# OpenAg_Signals_V6.net
KiCad netlist of a schematic drawn in EAGLE
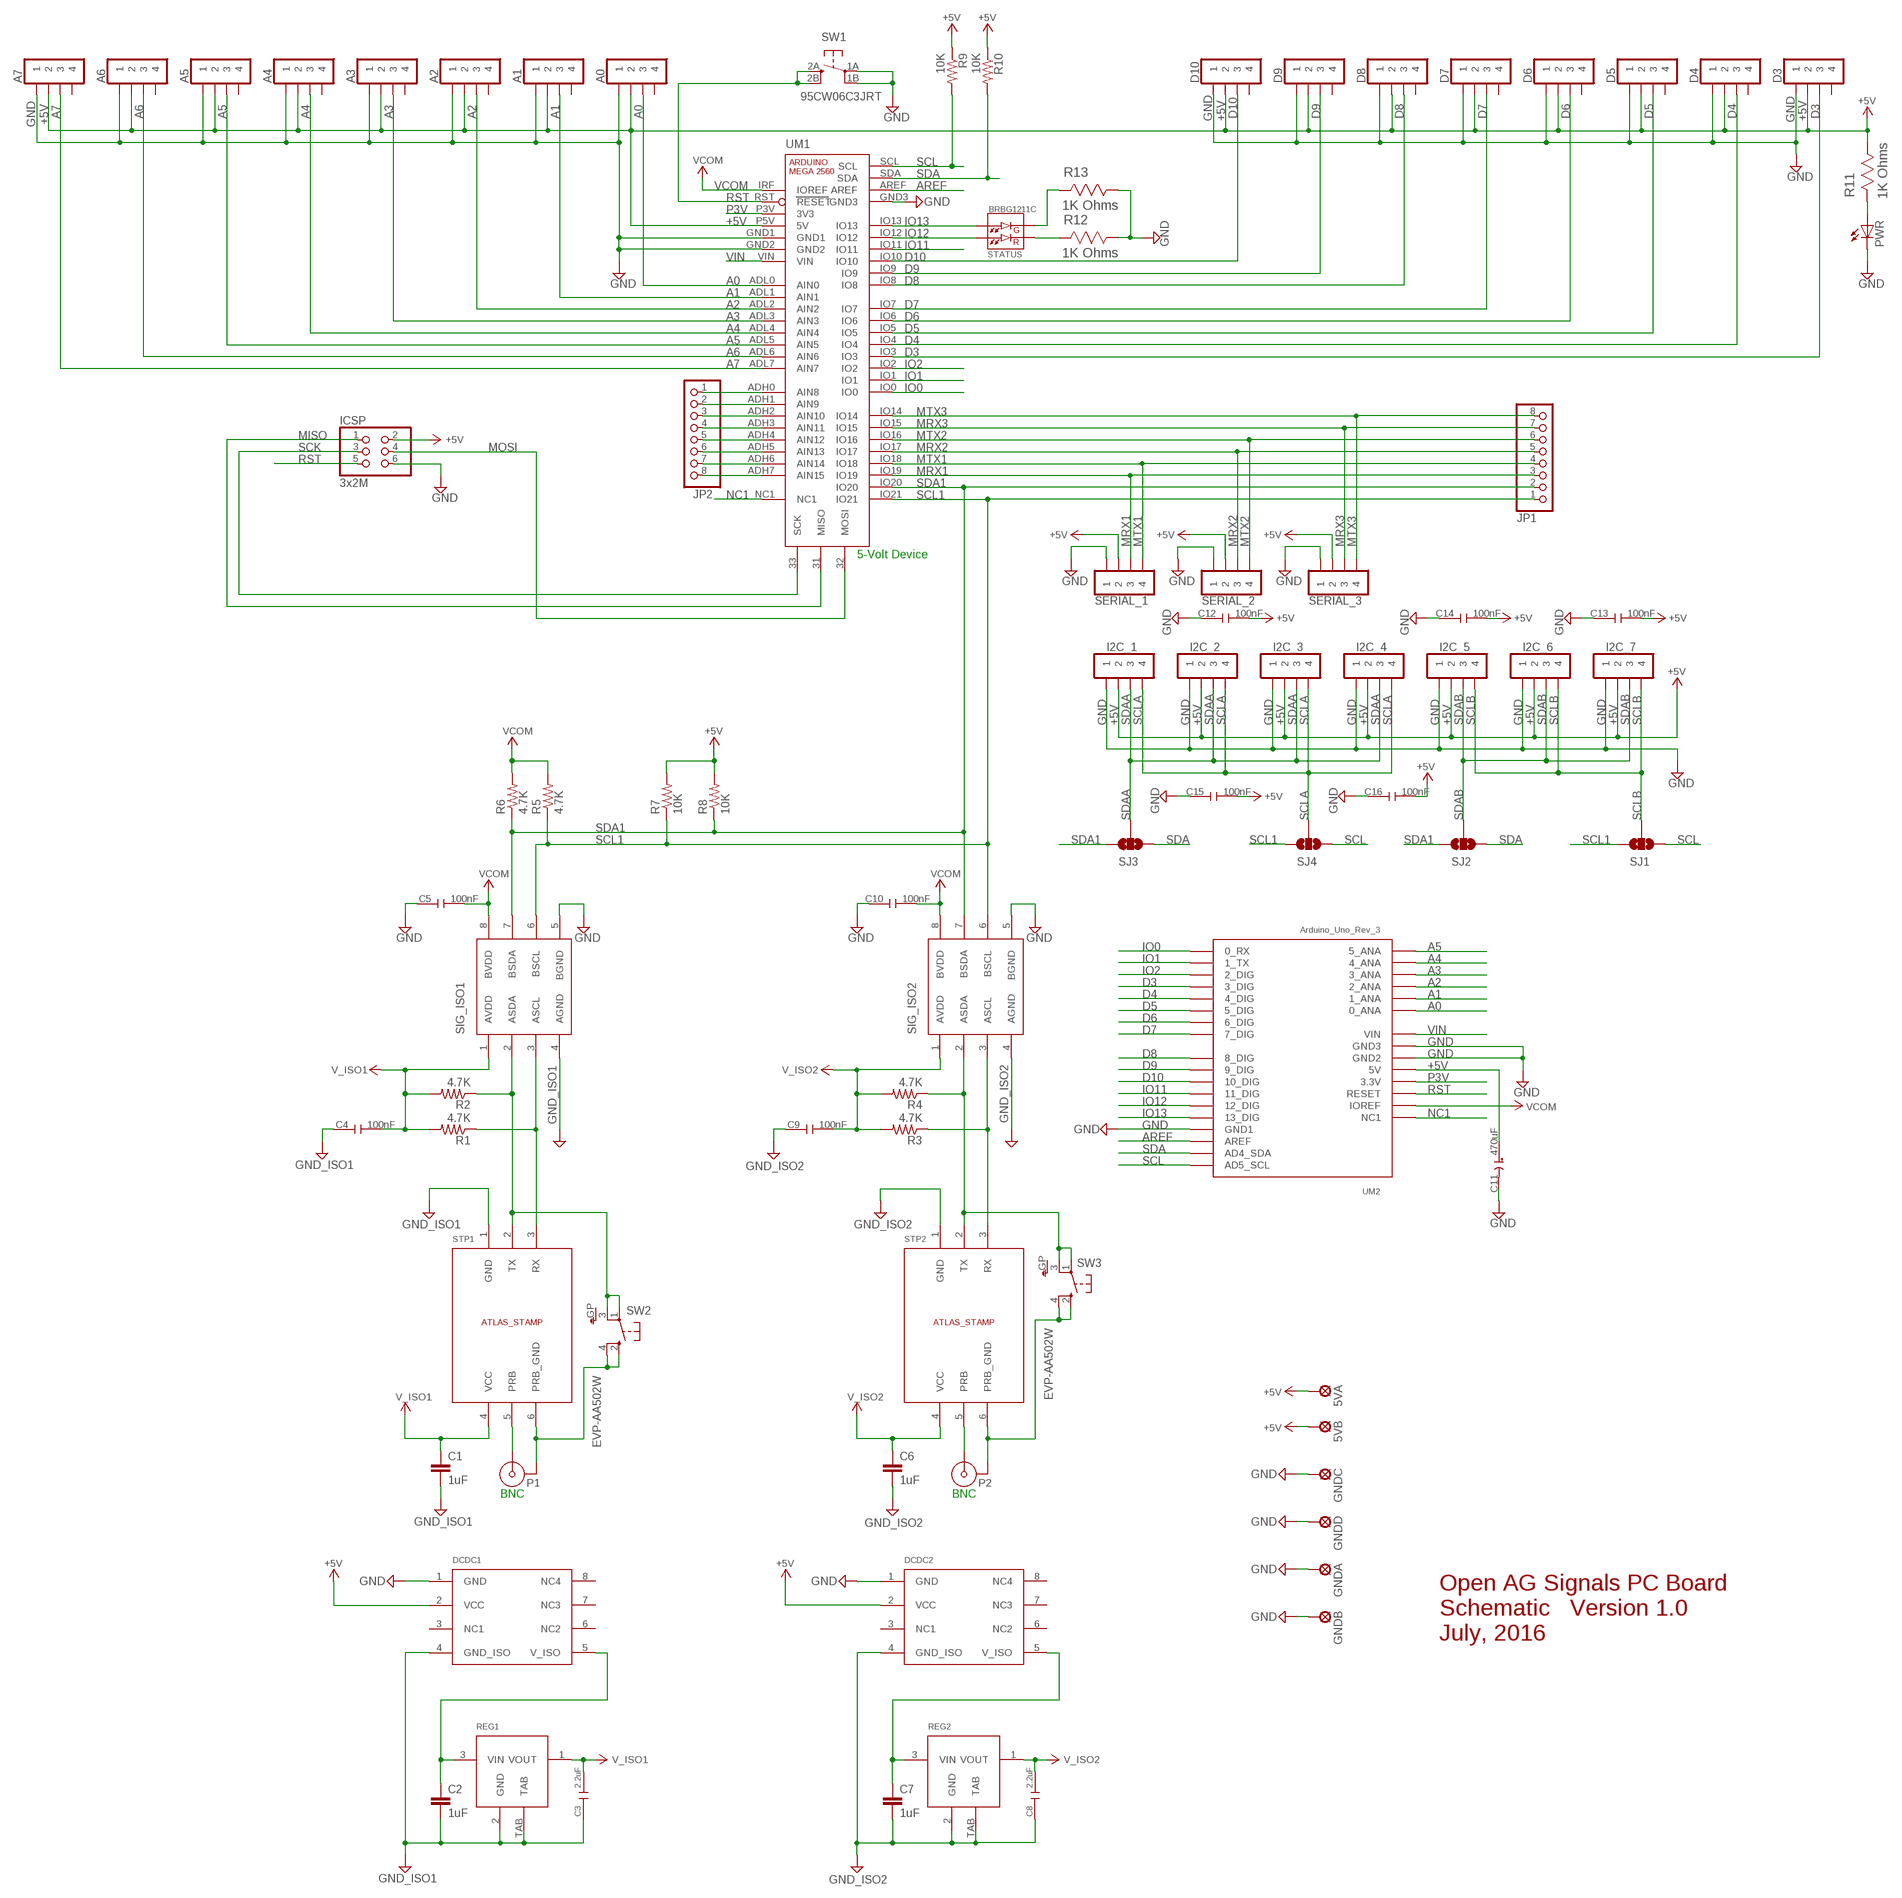
[diagram p0: schematic, sheet 1]

(export (version "E")
  (design (tool "Eeschema 10.0.6"))
  (components
    (comp (ref "5VA")
      (value "PAD070")
      (footprint "eagle-import:PAD070")
      (libsource (lib "eagle-import") (part "PAD070"))
    )
    (comp (ref "5VB")
      (value "PAD070")
      (footprint "eagle-import:PAD070")
      (libsource (lib "eagle-import") (part "PAD070"))
    )
    (comp (ref "A0")
      (value "MOLEX_0705430003")
      (footprint "eagle-import:MOLEX_0705430003")
      (libsource (lib "eagle-import") (part "MOLEX_0705430003"))
    )
    (comp (ref "A1")
      (value "MOLEX_0705430003")
      (footprint "eagle-import:MOLEX_0705430003")
      (libsource (lib "eagle-import") (part "MOLEX_0705430003"))
    )
    (comp (ref "A2")
      (value "MOLEX_0705430003")
      (footprint "eagle-import:MOLEX_0705430003")
      (libsource (lib "eagle-import") (part "MOLEX_0705430003"))
    )
    (comp (ref "A3")
      (value "MOLEX_0705430003")
      (footprint "eagle-import:MOLEX_0705430003")
      (libsource (lib "eagle-import") (part "MOLEX_0705430003"))
    )
    (comp (ref "A4")
      (value "MOLEX_0705430003")
      (footprint "eagle-import:MOLEX_0705430003")
      (libsource (lib "eagle-import") (part "MOLEX_0705430003"))
    )
    (comp (ref "A5")
      (value "MOLEX_0705430003")
      (footprint "eagle-import:MOLEX_0705430003")
      (libsource (lib "eagle-import") (part "MOLEX_0705430003"))
    )
    (comp (ref "A6")
      (value "MOLEX_0705430003")
      (footprint "eagle-import:MOLEX_0705430003")
      (libsource (lib "eagle-import") (part "MOLEX_0705430003"))
    )
    (comp (ref "A7")
      (value "MOLEX_0705430003")
      (footprint "eagle-import:MOLEX_0705430003")
      (libsource (lib "eagle-import") (part "MOLEX_0705430003"))
    )
    (comp (ref "C1")
      (value "1uF")
      (footprint "eagle-import:0805")
      (libsource (lib "eagle-import") (part "1UF-25V-10%(0805)"))
    )
    (comp (ref "C2")
      (value "1uF")
      (footprint "eagle-import:0805")
      (libsource (lib "eagle-import") (part "1UF-25V-10%(0805)"))
    )
    (comp (ref "C3")
      (value "2.2uF")
      (footprint "eagle-import:M0805")
      (libsource (lib "eagle-import") (part "CGA4J1X7R1V225K125AC"))
    )
    (comp (ref "C4")
      (value "C-N-100.0N-X7R-25V-10P-0805")
      (footprint "eagle-import:M0805")
      (libsource (lib "eagle-import") (part "C--?0805N-100.0N-X7R-25V-10P"))
    )
    (comp (ref "C5")
      (value "C-N-100.0N-X7R-25V-10P-0805")
      (footprint "eagle-import:M0805")
      (libsource (lib "eagle-import") (part "C--?0805N-100.0N-X7R-25V-10P"))
    )
    (comp (ref "C6")
      (value "1uF")
      (footprint "eagle-import:0805")
      (libsource (lib "eagle-import") (part "1UF-25V-10%(0805)"))
    )
    (comp (ref "C7")
      (value "1uF")
      (footprint "eagle-import:0805")
      (libsource (lib "eagle-import") (part "1UF-25V-10%(0805)"))
    )
    (comp (ref "C8")
      (value "2.2uF")
      (footprint "eagle-import:M0805")
      (libsource (lib "eagle-import") (part "CGA4J1X7R1V225K125AC"))
    )
    (comp (ref "C9")
      (value "C-N-100.0N-X7R-25V-10P-0805")
      (footprint "eagle-import:M0805")
      (libsource (lib "eagle-import") (part "C--?0805N-100.0N-X7R-25V-10P"))
    )
    (comp (ref "C10")
      (value "C-N-100.0N-X7R-25V-10P-0805")
      (footprint "eagle-import:M0805")
      (libsource (lib "eagle-import") (part "C--?0805N-100.0N-X7R-25V-10P"))
    )
    (comp (ref "C11")
      (value "T495X477K010ATE100")
      (footprint "eagle-import:M2917")
      (libsource (lib "eagle-import") (part "T495X477K010ATE100"))
    )
    (comp (ref "C12")
      (value "C-N-100.0N-X7R-25V-10P-0805")
      (footprint "eagle-import:M0805")
      (libsource (lib "eagle-import") (part "C--?0805N-100.0N-X7R-25V-10P"))
    )
    (comp (ref "C13")
      (value "C-N-100.0N-X7R-25V-10P-0805")
      (footprint "eagle-import:M0805")
      (libsource (lib "eagle-import") (part "C--?0805N-100.0N-X7R-25V-10P"))
    )
    (comp (ref "C14")
      (value "C-N-100.0N-X7R-25V-10P-0805")
      (footprint "eagle-import:M0805")
      (libsource (lib "eagle-import") (part "C--?0805N-100.0N-X7R-25V-10P"))
    )
    (comp (ref "C15")
      (value "C-N-100.0N-X7R-25V-10P-0805")
      (footprint "eagle-import:M0805")
      (libsource (lib "eagle-import") (part "C--?0805N-100.0N-X7R-25V-10P"))
    )
    (comp (ref "C16")
      (value "C-N-100.0N-X7R-25V-10P-0805")
      (footprint "eagle-import:M0805")
      (libsource (lib "eagle-import") (part "C--?0805N-100.0N-X7R-25V-10P"))
    )
    (comp (ref "D3")
      (value "MOLEX_0705430003")
      (footprint "eagle-import:MOLEX_0705430003")
      (libsource (lib "eagle-import") (part "MOLEX_0705430003"))
    )
    (comp (ref "D4")
      (value "MOLEX_0705430003")
      (footprint "eagle-import:MOLEX_0705430003")
      (libsource (lib "eagle-import") (part "MOLEX_0705430003"))
    )
    (comp (ref "D5")
      (value "MOLEX_0705430003")
      (footprint "eagle-import:MOLEX_0705430003")
      (libsource (lib "eagle-import") (part "MOLEX_0705430003"))
    )
    (comp (ref "D6")
      (value "MOLEX_0705430003")
      (footprint "eagle-import:MOLEX_0705430003")
      (libsource (lib "eagle-import") (part "MOLEX_0705430003"))
    )
    (comp (ref "D7")
      (value "MOLEX_0705430003")
      (footprint "eagle-import:MOLEX_0705430003")
      (libsource (lib "eagle-import") (part "MOLEX_0705430003"))
    )
    (comp (ref "D8")
      (value "MOLEX_0705430003")
      (footprint "eagle-import:MOLEX_0705430003")
      (libsource (lib "eagle-import") (part "MOLEX_0705430003"))
    )
    (comp (ref "D9")
      (value "MOLEX_0705430003")
      (footprint "eagle-import:MOLEX_0705430003")
      (libsource (lib "eagle-import") (part "MOLEX_0705430003"))
    )
    (comp (ref "D10")
      (value "MOLEX_0705430003")
      (footprint "eagle-import:MOLEX_0705430003")
      (libsource (lib "eagle-import") (part "MOLEX_0705430003"))
    )
    (comp (ref "DCDC1")
      (value "RECOM_R1SE_0505_R")
      (footprint "eagle-import:RECOM_R1SE_0505_R")
      (libsource (lib "eagle-import") (part "RECOM_R1SE_0505_R"))
    )
    (comp (ref "DCDC2")
      (value "RECOM_R1SE_0505_R")
      (footprint "eagle-import:RECOM_R1SE_0505_R")
      (libsource (lib "eagle-import") (part "RECOM_R1SE_0505_R"))
    )
    (comp (ref "GNDA")
      (value "PAD070")
      (footprint "eagle-import:PAD070")
      (libsource (lib "eagle-import") (part "PAD070"))
    )
    (comp (ref "GNDB")
      (value "PAD070")
      (footprint "eagle-import:PAD070")
      (libsource (lib "eagle-import") (part "PAD070"))
    )
    (comp (ref "GNDC")
      (value "PAD070")
      (footprint "eagle-import:PAD070")
      (libsource (lib "eagle-import") (part "PAD070"))
    )
    (comp (ref "GNDD")
      (value "PAD070")
      (footprint "eagle-import:PAD070")
      (libsource (lib "eagle-import") (part "PAD070"))
    )
    (comp (ref "I2C_1")
      (value "MOLEX_0705430003")
      (footprint "eagle-import:MOLEX_0705430003")
      (libsource (lib "eagle-import") (part "MOLEX_0705430003"))
    )
    (comp (ref "I2C_2")
      (value "MOLEX_0705430003")
      (footprint "eagle-import:MOLEX_0705430003")
      (libsource (lib "eagle-import") (part "MOLEX_0705430003"))
    )
    (comp (ref "I2C_3")
      (value "MOLEX_0705430003")
      (footprint "eagle-import:MOLEX_0705430003")
      (libsource (lib "eagle-import") (part "MOLEX_0705430003"))
    )
    (comp (ref "I2C_4")
      (value "MOLEX_0705430003")
      (footprint "eagle-import:MOLEX_0705430003")
      (libsource (lib "eagle-import") (part "MOLEX_0705430003"))
    )
    (comp (ref "I2C_5")
      (value "MOLEX_0705430003")
      (footprint "eagle-import:MOLEX_0705430003")
      (libsource (lib "eagle-import") (part "MOLEX_0705430003"))
    )
    (comp (ref "I2C_6")
      (value "MOLEX_0705430003")
      (footprint "eagle-import:MOLEX_0705430003")
      (libsource (lib "eagle-import") (part "MOLEX_0705430003"))
    )
    (comp (ref "I2C_7")
      (value "MOLEX_0705430003")
      (footprint "eagle-import:MOLEX_0705430003")
      (libsource (lib "eagle-import") (part "MOLEX_0705430003"))
    )
    (comp (ref "ICSP")
      (value "3x2M")
      (footprint "eagle-import:2X03")
      (libsource (lib "eagle-import") (part "PINHD-2X3"))
    )
    (comp (ref "JP1")
      (value "PINHD-1X8BIG")
      (footprint "eagle-import:1X08-BIG")
      (libsource (lib "eagle-import") (part "PINHD-1X8BIG"))
    )
    (comp (ref "JP2")
      (value "PINHD-1X8BIG")
      (footprint "eagle-import:1X08-BIG")
      (libsource (lib "eagle-import") (part "PINHD-1X8BIG"))
    )
    (comp (ref "P1")
      (value "BNC_TE_1_1337542_0")
      (footprint "eagle-import:BNC_FEMALE_PANEL_RGT_ANGLE_MNT")
      (libsource (lib "eagle-import") (part "BNC_TE_1_1337542_0"))
    )
    (comp (ref "P2")
      (value "BNC_TE_1_1337542_0")
      (footprint "eagle-import:BNC_FEMALE_PANEL_RGT_ANGLE_MNT")
      (libsource (lib "eagle-import") (part "BNC_TE_1_1337542_0"))
    )
    (comp (ref "PWR")
      (value "LED_LEDCHIPLED_0805")
      (footprint "eagle-import:LED_CHIPLED_0805")
      (libsource (lib "eagle-import") (part "LED_LEDCHIPLED_0805"))
    )
    (comp (ref "R1")
      (value "4.7K")
      (footprint "eagle-import:0805")
      (libsource (lib "eagle-import") (part "RESISTOR"))
    )
    (comp (ref "R2")
      (value "4.7K")
      (footprint "eagle-import:0805")
      (libsource (lib "eagle-import") (part "RESISTOR"))
    )
    (comp (ref "R3")
      (value "4.7K")
      (footprint "eagle-import:0805")
      (libsource (lib "eagle-import") (part "RESISTOR"))
    )
    (comp (ref "R4")
      (value "4.7K")
      (footprint "eagle-import:0805")
      (libsource (lib "eagle-import") (part "RESISTOR"))
    )
    (comp (ref "R5")
      (value "4.7K")
      (footprint "eagle-import:0805")
      (libsource (lib "eagle-import") (part "RESISTOR"))
    )
    (comp (ref "R6")
      (value "4.7K")
      (footprint "eagle-import:0805")
      (libsource (lib "eagle-import") (part "RESISTOR"))
    )
    (comp (ref "R7")
      (value "10K")
      (footprint "eagle-import:0603-RES")
      (libsource (lib "eagle-import") (part "10KOHM1/10W1%(0603)0603"))
    )
    (comp (ref "R8")
      (value "10K")
      (footprint "eagle-import:0603-RES")
      (libsource (lib "eagle-import") (part "10KOHM1/10W1%(0603)0603"))
    )
    (comp (ref "R9")
      (value "10K")
      (footprint "eagle-import:0603-RES")
      (libsource (lib "eagle-import") (part "10KOHM1/10W1%(0603)0603"))
    )
    (comp (ref "R10")
      (value "10K")
      (footprint "eagle-import:0603-RES")
      (libsource (lib "eagle-import") (part "10KOHM1/10W1%(0603)0603"))
    )
    (comp (ref "R11")
      (value "1K Ohms")
      (footprint "eagle-import:RESC1608X60N")
      (fields (field (name "MPN") "CPF0603F1K1C1") (field (name "TOLERANCE") "± 1%"))
      (libsource (lib "eagle-import") (part "CPF0603F1K1C1"))
    )
    (comp (ref "R12")
      (value "1K Ohms")
      (footprint "eagle-import:RESC1608X60N")
      (fields (field (name "MPN") "CPF0603F1K1C1") (field (name "TOLERANCE") "± 1%"))
      (libsource (lib "eagle-import") (part "CPF0603F1K1C1"))
    )
    (comp (ref "R13")
      (value "1K Ohms")
      (footprint "eagle-import:RESC1608X60N")
      (fields (field (name "MPN") "CPF0603F1K1C1") (field (name "TOLERANCE") "± 1%"))
      (libsource (lib "eagle-import") (part "CPF0603F1K1C1"))
    )
    (comp (ref "REG1")
      (value "LD2981ABU50TR")
      (footprint "eagle-import:SOT89")
      (libsource (lib "eagle-import") (part "LD2981ABU50TR"))
    )
    (comp (ref "REG2")
      (value "LD2981ABU50TR")
      (footprint "eagle-import:SOT89")
      (libsource (lib "eagle-import") (part "LD2981ABU50TR"))
    )
    (comp (ref "SERIAL_1")
      (value "MOLEX_0705430003")
      (footprint "eagle-import:MOLEX_0705430003")
      (libsource (lib "eagle-import") (part "MOLEX_0705430003"))
    )
    (comp (ref "SERIAL_2")
      (value "MOLEX_0705430003")
      (footprint "eagle-import:MOLEX_0705430003")
      (libsource (lib "eagle-import") (part "MOLEX_0705430003"))
    )
    (comp (ref "SERIAL_3")
      (value "MOLEX_0705430003")
      (footprint "eagle-import:MOLEX_0705430003")
      (libsource (lib "eagle-import") (part "MOLEX_0705430003"))
    )
    (comp (ref "SIG_ISO1")
      (value "SI8600AC-B-IS")
      (footprint "eagle-import:SO8ISO")
      (libsource (lib "eagle-import") (part "SI8600AC-B-IS"))
    )
    (comp (ref "SIG_ISO2")
      (value "SI8600AC-B-IS")
      (footprint "eagle-import:SO8ISO")
      (libsource (lib "eagle-import") (part "SI8600AC-B-IS"))
    )
    (comp (ref "SJ1")
      (value "SOLDERJUMPER_2WAYT")
      (footprint "eagle-import:SJ_2")
      (libsource (lib "eagle-import") (part "SOLDERJUMPER_2WAYT"))
    )
    (comp (ref "SJ2")
      (value "SOLDERJUMPER_2WAYT")
      (footprint "eagle-import:SJ_2")
      (libsource (lib "eagle-import") (part "SOLDERJUMPER_2WAYT"))
    )
    (comp (ref "SJ3")
      (value "SOLDERJUMPER_2WAYT")
      (footprint "eagle-import:SJ_2")
      (libsource (lib "eagle-import") (part "SOLDERJUMPER_2WAYT"))
    )
    (comp (ref "SJ4")
      (value "SOLDERJUMPER_2WAYT")
      (footprint "eagle-import:SJ_2")
      (libsource (lib "eagle-import") (part "SOLDERJUMPER_2WAYT"))
    )
    (comp (ref "STATUS")
      (value "LED-REDGRN-BRBG1211C")
      (footprint "eagle-import:BILED-0605")
      (libsource (lib "eagle-import") (part "LED-REDGRN-BRBG1211C"))
    )
    (comp (ref "STP1")
      (value "ATLAS_SCIENTIFIC_STAMP")
      (footprint "eagle-import:ATLAS_SCIENTIFIC_STAMP")
      (libsource (lib "eagle-import") (part "ATLAS_SCIENTIFIC_STAMP"))
    )
    (comp (ref "STP2")
      (value "ATLAS_SCIENTIFIC_STAMP")
      (footprint "eagle-import:ATLAS_SCIENTIFIC_STAMP")
      (libsource (lib "eagle-import") (part "ATLAS_SCIENTIFIC_STAMP"))
    )
    (comp (ref "SW1")
      (value "95CW06C3JRT")
      (footprint "eagle-import:GRAYHILL_95CW06C3JRT")
      (libsource (lib "eagle-import") (part "95CW06C3JRT"))
    )
    (comp (ref "SW2")
      (value "EVP-AA502W")
      (footprint "eagle-import:PANASONIC-EVP-AA502W")
      (fields (field (name "VAL") "EVP-AA502W"))
      (libsource (lib "eagle-import") (part "EVP-AA502W"))
    )
    (comp (ref "SW3")
      (value "EVP-AA502W")
      (footprint "eagle-import:PANASONIC-EVP-AA502W")
      (fields (field (name "VAL") "EVP-AA502W"))
      (libsource (lib "eagle-import") (part "EVP-AA502W"))
    )
    (comp (ref "UM1")
      (value "ARDUINO_MEGA_2560_R3_SIDES")
      (footprint "eagle-import:ARDUINO_MEGA_2560_R3_CONNECTORS")
      (libsource (lib "eagle-import") (part "ARDUINO_MEGA_2560_R3_SIDES"))
    )
    (comp (ref "UM2")
      (value "ARDUINO_UNO_REV3_SOCKET")
      (footprint "eagle-import:ARDUINO_UNO_REV3_SOCKET")
      (libsource (lib "eagle-import") (part "ARDUINO_UNO_REV3_SOCKET"))
    )
  )
  (nets
    (net (code "1") (name "+5V") (class "Default")
      (node (ref "5VA") (pin "1") (pinfunction "MP_1") (pintype "passive"))
      (node (ref "5VB") (pin "1") (pinfunction "MP_1") (pintype "passive"))
      (node (ref "A0") (pin "2") (pinfunction "2_2") (pintype "passive"))
      (node (ref "A1") (pin "2") (pinfunction "2_2") (pintype "passive"))
      (node (ref "A2") (pin "2") (pinfunction "2_2") (pintype "passive"))
      (node (ref "A3") (pin "2") (pinfunction "2_2") (pintype "passive"))
      (node (ref "A4") (pin "2") (pinfunction "2_2") (pintype "passive"))
      (node (ref "A5") (pin "2") (pinfunction "2_2") (pintype "passive"))
      (node (ref "A6") (pin "2") (pinfunction "2_2") (pintype "passive"))
      (node (ref "A7") (pin "2") (pinfunction "2_2") (pintype "passive"))
      (node (ref "C11") (pin "P") (pinfunction "P_P") (pintype "passive"))
      (node (ref "C12") (pin "2") (pinfunction "2_2") (pintype "passive"))
      (node (ref "C13") (pin "2") (pinfunction "2_2") (pintype "passive"))
      (node (ref "C14") (pin "2") (pinfunction "2_2") (pintype "passive"))
      (node (ref "C15") (pin "2") (pinfunction "2_2") (pintype "passive"))
      (node (ref "C16") (pin "2") (pinfunction "2_2") (pintype "passive"))
      (node (ref "D10") (pin "2") (pinfunction "2_2") (pintype "passive"))
      (node (ref "D3") (pin "2") (pinfunction "2_2") (pintype "passive"))
      (node (ref "D4") (pin "2") (pinfunction "2_2") (pintype "passive"))
      (node (ref "D5") (pin "2") (pinfunction "2_2") (pintype "passive"))
      (node (ref "D6") (pin "2") (pinfunction "2_2") (pintype "passive"))
      (node (ref "D7") (pin "2") (pinfunction "2_2") (pintype "passive"))
      (node (ref "D8") (pin "2") (pinfunction "2_2") (pintype "passive"))
      (node (ref "D9") (pin "2") (pinfunction "2_2") (pintype "passive"))
      (node (ref "DCDC1") (pin "2") (pinfunction "VCC_2") (pintype "bidirectional"))
      (node (ref "DCDC2") (pin "2") (pinfunction "VCC_2") (pintype "bidirectional"))
      (node (ref "I2C_1") (pin "2") (pinfunction "2_2") (pintype "passive"))
      (node (ref "I2C_2") (pin "2") (pinfunction "2_2") (pintype "passive"))
      (node (ref "I2C_3") (pin "2") (pinfunction "2_2") (pintype "passive"))
      (node (ref "I2C_4") (pin "2") (pinfunction "2_2") (pintype "passive"))
      (node (ref "I2C_5") (pin "2") (pinfunction "2_2") (pintype "passive"))
      (node (ref "I2C_6") (pin "2") (pinfunction "2_2") (pintype "passive"))
      (node (ref "I2C_7") (pin "2") (pinfunction "2_2") (pintype "passive"))
      (node (ref "ICSP") (pin "2") (pinfunction "2_2") (pintype "passive"))
      (node (ref "R10") (pin "1") (pinfunction "1_1") (pintype "passive"))
      (node (ref "R11") (pin "1") (pinfunction "1_1") (pintype "passive"))
      (node (ref "R7") (pin "2") (pinfunction "2_2") (pintype "passive"))
      (node (ref "R8") (pin "2") (pinfunction "2_2") (pintype "passive"))
      (node (ref "R9") (pin "1") (pinfunction "1_1") (pintype "passive"))
      (node (ref "SERIAL_1") (pin "2") (pinfunction "2_2") (pintype "passive"))
      (node (ref "SERIAL_2") (pin "2") (pinfunction "2_2") (pintype "passive"))
      (node (ref "SERIAL_3") (pin "2") (pinfunction "2_2") (pintype "passive"))
      (node (ref "UM1") (pin "P5V") (pinfunction "5V_P5V") (pintype "bidirectional"))
      (node (ref "UM2") (pin "PWR_5V") (pinfunction "5V_PWR_5V") (pintype "passive"))
    )
    (net (code "2") (name "/A0") (class "Default")
      (node (ref "A0") (pin "3") (pinfunction "3_3") (pintype "passive"))
      (node (ref "UM1") (pin "ADL0") (pinfunction "AIN0_ADL0") (pintype "bidirectional"))
      (node (ref "UM2") (pin "AD0") (pinfunction "0_ANA_AD0") (pintype "passive"))
    )
    (net (code "3") (name "/A1") (class "Default")
      (node (ref "A1") (pin "3") (pinfunction "3_3") (pintype "passive"))
      (node (ref "UM1") (pin "ADL1") (pinfunction "AIN1_ADL1") (pintype "bidirectional"))
      (node (ref "UM2") (pin "AD1") (pinfunction "1_ANA_AD1") (pintype "passive"))
    )
    (net (code "4") (name "/A2") (class "Default")
      (node (ref "A2") (pin "3") (pinfunction "3_3") (pintype "passive"))
      (node (ref "UM1") (pin "ADL2") (pinfunction "AIN2_ADL2") (pintype "bidirectional"))
      (node (ref "UM2") (pin "AD2") (pinfunction "2_ANA_AD2") (pintype "passive"))
    )
    (net (code "5") (name "/A3") (class "Default")
      (node (ref "A3") (pin "3") (pinfunction "3_3") (pintype "passive"))
      (node (ref "UM1") (pin "ADL3") (pinfunction "AIN3_ADL3") (pintype "bidirectional"))
      (node (ref "UM2") (pin "AD3") (pinfunction "3_ANA_AD3") (pintype "passive"))
    )
    (net (code "6") (name "/A4") (class "Default")
      (node (ref "A4") (pin "3") (pinfunction "3_3") (pintype "passive"))
      (node (ref "UM1") (pin "ADL4") (pinfunction "AIN4_ADL4") (pintype "bidirectional"))
      (node (ref "UM2") (pin "AD4") (pinfunction "4_ANA_AD4") (pintype "passive"))
    )
    (net (code "7") (name "/A5") (class "Default")
      (node (ref "A5") (pin "3") (pinfunction "3_3") (pintype "passive"))
      (node (ref "UM1") (pin "ADL5") (pinfunction "AIN5_ADL5") (pintype "bidirectional"))
      (node (ref "UM2") (pin "AD5") (pinfunction "5_ANA_AD5") (pintype "passive"))
    )
    (net (code "8") (name "/A6") (class "Default")
      (node (ref "A6") (pin "3") (pinfunction "3_3") (pintype "passive"))
      (node (ref "UM1") (pin "ADL6") (pinfunction "AIN6_ADL6") (pintype "bidirectional"))
    )
    (net (code "9") (name "/A7") (class "Default")
      (node (ref "A7") (pin "3") (pinfunction "3_3") (pintype "passive"))
      (node (ref "UM1") (pin "ADL7") (pinfunction "AIN7_ADL7") (pintype "bidirectional"))
    )
    (net (code "10") (name "/AREF") (class "Default")
      (node (ref "UM1") (pin "AREF") (pinfunction "AREF_AREF") (pintype "bidirectional"))
      (node (ref "UM2") (pin "IOH15") (pinfunction "AREF_IOH15") (pintype "passive"))
    )
    (net (code "11") (name "/D3") (class "Default")
      (node (ref "D3") (pin "3") (pinfunction "3_3") (pintype "passive"))
      (node (ref "UM1") (pin "IO3") (pinfunction "IO3_IO3") (pintype "bidirectional"))
      (node (ref "UM2") (pin "IOL3") (pinfunction "3_DIG_IOL3") (pintype "passive"))
    )
    (net (code "12") (name "/D4") (class "Default")
      (node (ref "D4") (pin "3") (pinfunction "3_3") (pintype "passive"))
      (node (ref "UM1") (pin "IO4") (pinfunction "IO4_IO4") (pintype "bidirectional"))
      (node (ref "UM2") (pin "IOL4") (pinfunction "4_DIG_IOL4") (pintype "passive"))
    )
    (net (code "13") (name "/D5") (class "Default")
      (node (ref "D5") (pin "3") (pinfunction "3_3") (pintype "passive"))
      (node (ref "UM1") (pin "IO5") (pinfunction "IO5_IO5") (pintype "bidirectional"))
      (node (ref "UM2") (pin "IOL5") (pinfunction "5_DIG_IOL5") (pintype "passive"))
    )
    (net (code "14") (name "/D6") (class "Default")
      (node (ref "D6") (pin "3") (pinfunction "3_3") (pintype "passive"))
      (node (ref "UM1") (pin "IO6") (pinfunction "IO6_IO6") (pintype "bidirectional"))
      (node (ref "UM2") (pin "IOL6") (pinfunction "6_DIG_IOL6") (pintype "passive"))
    )
    (net (code "15") (name "/D7") (class "Default")
      (node (ref "D7") (pin "3") (pinfunction "3_3") (pintype "passive"))
      (node (ref "UM1") (pin "IO7") (pinfunction "IO7_IO7") (pintype "bidirectional"))
      (node (ref "UM2") (pin "IOL7") (pinfunction "7_DIG_IOL7") (pintype "passive"))
    )
    (net (code "16") (name "/D8") (class "Default")
      (node (ref "D8") (pin "3") (pinfunction "3_3") (pintype "passive"))
      (node (ref "UM1") (pin "IO8") (pinfunction "IO8_IO8") (pintype "bidirectional"))
      (node (ref "UM2") (pin "IOH8") (pinfunction "8_DIG_IOH8") (pintype "passive"))
    )
    (net (code "17") (name "/D9") (class "Default")
      (node (ref "D9") (pin "3") (pinfunction "3_3") (pintype "passive"))
      (node (ref "UM1") (pin "IO9") (pinfunction "IO9_IO9") (pintype "bidirectional"))
      (node (ref "UM2") (pin "IOH9") (pinfunction "9_DIG_IOH9") (pintype "passive"))
    )
    (net (code "18") (name "/D10") (class "Default")
      (node (ref "D10") (pin "3") (pinfunction "3_3") (pintype "passive"))
      (node (ref "UM1") (pin "IO10") (pinfunction "IO10_IO10") (pintype "bidirectional"))
      (node (ref "UM2") (pin "IOH10") (pinfunction "10_DIG_IOH10") (pintype "passive"))
    )
    (net (code "19") (name "/IO0") (class "Default")
      (node (ref "UM1") (pin "IO0") (pinfunction "IO0_IO0") (pintype "bidirectional"))
      (node (ref "UM2") (pin "IOL0") (pinfunction "0_RX_IOL0") (pintype "passive"))
    )
    (net (code "20") (name "/IO1") (class "Default")
      (node (ref "UM1") (pin "IO1") (pinfunction "IO1_IO1") (pintype "bidirectional"))
      (node (ref "UM2") (pin "IOL1") (pinfunction "1_TX_IOL1") (pintype "passive"))
    )
    (net (code "21") (name "/IO2") (class "Default")
      (node (ref "UM1") (pin "IO2") (pinfunction "IO2_IO2") (pintype "bidirectional"))
      (node (ref "UM2") (pin "IOL2") (pinfunction "2_DIG_IOL2") (pintype "passive"))
    )
    (net (code "22") (name "/IO11") (class "Default")
      (node (ref "UM1") (pin "IO11") (pinfunction "IO11_IO11") (pintype "bidirectional"))
      (node (ref "UM2") (pin "IOH11") (pinfunction "11_DIG_IOH11") (pintype "passive"))
    )
    (net (code "23") (name "/IO12") (class "Default")
      (node (ref "STATUS") (pin "1") (pinfunction "RA_1") (pintype "passive"))
      (node (ref "UM1") (pin "IO12") (pinfunction "IO12_IO12") (pintype "bidirectional"))
      (node (ref "UM2") (pin "IOH12") (pinfunction "12_DIG_IOH12") (pintype "passive"))
    )
    (net (code "24") (name "/IO13") (class "Default")
      (node (ref "STATUS") (pin "3") (pinfunction "GA_3") (pintype "passive"))
      (node (ref "UM1") (pin "IO13") (pinfunction "IO13_IO13") (pintype "bidirectional"))
      (node (ref "UM2") (pin "IOH13") (pinfunction "13_DIG_IOH13") (pintype "passive"))
    )
    (net (code "25") (name "/MISO") (class "Default")
      (node (ref "ICSP") (pin "1") (pinfunction "1_1") (pintype "passive"))
      (node (ref "UM1") (pin "31") (pinfunction "MISO_31") (pintype "bidirectional"))
    )
    (net (code "26") (name "/MOSI") (class "Default")
      (node (ref "ICSP") (pin "4") (pinfunction "4_4") (pintype "passive"))
      (node (ref "UM1") (pin "32") (pinfunction "MOSI_32") (pintype "bidirectional"))
    )
    (net (code "27") (name "/MRX1") (class "Default")
      (node (ref "JP1") (pin "3") (pinfunction "3_3") (pintype "passive"))
      (node (ref "SERIAL_1") (pin "3") (pinfunction "3_3") (pintype "passive"))
      (node (ref "UM1") (pin "IO19") (pinfunction "IO19_IO19") (pintype "bidirectional"))
    )
    (net (code "28") (name "/MRX2") (class "Default")
      (node (ref "JP1") (pin "5") (pinfunction "5_5") (pintype "passive"))
      (node (ref "SERIAL_2") (pin "3") (pinfunction "3_3") (pintype "passive"))
      (node (ref "UM1") (pin "IO17") (pinfunction "IO17_IO17") (pintype "bidirectional"))
    )
    (net (code "29") (name "/MRX3") (class "Default")
      (node (ref "JP1") (pin "7") (pinfunction "7_7") (pintype "passive"))
      (node (ref "SERIAL_3") (pin "3") (pinfunction "3_3") (pintype "passive"))
      (node (ref "UM1") (pin "IO15") (pinfunction "IO15_IO15") (pintype "bidirectional"))
    )
    (net (code "30") (name "/MTX1") (class "Default")
      (node (ref "JP1") (pin "4") (pinfunction "4_4") (pintype "passive"))
      (node (ref "SERIAL_1") (pin "4") (pinfunction "4_4") (pintype "passive"))
      (node (ref "UM1") (pin "IO18") (pinfunction "IO18_IO18") (pintype "bidirectional"))
    )
    (net (code "31") (name "/MTX2") (class "Default")
      (node (ref "JP1") (pin "6") (pinfunction "6_6") (pintype "passive"))
      (node (ref "SERIAL_2") (pin "4") (pinfunction "4_4") (pintype "passive"))
      (node (ref "UM1") (pin "IO16") (pinfunction "IO16_IO16") (pintype "bidirectional"))
    )
    (net (code "32") (name "/MTX3") (class "Default")
      (node (ref "JP1") (pin "8") (pinfunction "8_8") (pintype "passive"))
      (node (ref "SERIAL_3") (pin "4") (pinfunction "4_4") (pintype "passive"))
      (node (ref "UM1") (pin "IO14") (pinfunction "IO14_IO14") (pintype "bidirectional"))
    )
    (net (code "33") (name "/NC1") (class "Default")
      (node (ref "UM1") (pin "NC1") (pinfunction "NC1_NC1") (pintype "bidirectional"))
      (node (ref "UM2") (pin "PWR_NC") (pinfunction "NC1_PWR_NC") (pintype "passive"))
    )
    (net (code "34") (name "/P3V") (class "Default")
      (node (ref "UM1") (pin "P3V") (pinfunction "3V3_P3V") (pintype "bidirectional"))
      (node (ref "UM2") (pin "PWR_3_3V") (pinfunction "3.3V_PWR_3_3V") (pintype "passive"))
    )
    (net (code "35") (name "/RST") (class "Default")
      (node (ref "ICSP") (pin "5") (pinfunction "5_5") (pintype "passive"))
      (node (ref "SW1") (pin "2A") (pinfunction "PB1_2A") (pintype "passive"))
      (node (ref "SW1") (pin "2B") (pinfunction "PB2_2B") (pintype "passive"))
      (node (ref "UM1") (pin "RST") (pinfunction "RESET_RST") (pintype "input"))
      (node (ref "UM2") (pin "PWR_RESET") (pinfunction "RESET_PWR_RESET") (pintype "passive"))
    )
    (net (code "36") (name "/SCK") (class "Default")
      (node (ref "ICSP") (pin "3") (pinfunction "3_3") (pintype "passive"))
      (node (ref "UM1") (pin "33") (pinfunction "SCK_33") (pintype "bidirectional"))
    )
    (net (code "37") (name "/SCL") (class "Default")
      (node (ref "R9") (pin "2") (pinfunction "2_2") (pintype "passive"))
      (node (ref "SJ1") (pin "1") (pinfunction "1_1") (pintype "passive"))
      (node (ref "SJ4") (pin "1") (pinfunction "1_1") (pintype "passive"))
      (node (ref "UM1") (pin "SCL") (pinfunction "SCL_SCL") (pintype "bidirectional"))
      (node (ref "UM2") (pin "IOH17") (pinfunction "AD5_SCL_IOH17") (pintype "passive"))
    )
    (net (code "38") (name "/SCL1") (class "Default")
      (node (ref "JP1") (pin "1") (pinfunction "1_1") (pintype "passive"))
      (node (ref "R5") (pin "1") (pinfunction "1_1") (pintype "passive"))
      (node (ref "R7") (pin "1") (pinfunction "1_1") (pintype "passive"))
      (node (ref "SIG_ISO1") (pin "6") (pinfunction "BSCL_6") (pintype "bidirectional"))
      (node (ref "SIG_ISO2") (pin "6") (pinfunction "BSCL_6") (pintype "bidirectional"))
      (node (ref "SJ1") (pin "3") (pinfunction "3_3") (pintype "passive"))
      (node (ref "SJ4") (pin "3") (pinfunction "3_3") (pintype "passive"))
      (node (ref "UM1") (pin "IO21") (pinfunction "IO21_IO21") (pintype "bidirectional"))
    )
    (net (code "39") (name "/SCLA") (class "Default")
      (node (ref "I2C_1") (pin "4") (pinfunction "4_4") (pintype "passive"))
      (node (ref "I2C_2") (pin "4") (pinfunction "4_4") (pintype "passive"))
      (node (ref "I2C_3") (pin "4") (pinfunction "4_4") (pintype "passive"))
      (node (ref "I2C_4") (pin "4") (pinfunction "4_4") (pintype "passive"))
      (node (ref "SJ4") (pin "2") (pinfunction "2_2") (pintype "passive"))
    )
    (net (code "40") (name "/SCLB") (class "Default")
      (node (ref "I2C_5") (pin "4") (pinfunction "4_4") (pintype "passive"))
      (node (ref "I2C_6") (pin "4") (pinfunction "4_4") (pintype "passive"))
      (node (ref "I2C_7") (pin "4") (pinfunction "4_4") (pintype "passive"))
      (node (ref "SJ1") (pin "2") (pinfunction "2_2") (pintype "passive"))
    )
    (net (code "41") (name "/SDA") (class "Default")
      (node (ref "R10") (pin "2") (pinfunction "2_2") (pintype "passive"))
      (node (ref "SJ2") (pin "1") (pinfunction "1_1") (pintype "passive"))
      (node (ref "SJ3") (pin "1") (pinfunction "1_1") (pintype "passive"))
      (node (ref "UM1") (pin "SDA") (pinfunction "SDA_SDA") (pintype "bidirectional"))
      (node (ref "UM2") (pin "IOH16") (pinfunction "AD4_SDA_IOH16") (pintype "passive"))
    )
    (net (code "42") (name "/SDA1") (class "Default")
      (node (ref "JP1") (pin "2") (pinfunction "2_2") (pintype "passive"))
      (node (ref "R6") (pin "1") (pinfunction "1_1") (pintype "passive"))
      (node (ref "R8") (pin "1") (pinfunction "1_1") (pintype "passive"))
      (node (ref "SIG_ISO1") (pin "7") (pinfunction "BSDA_7") (pintype "bidirectional"))
      (node (ref "SIG_ISO2") (pin "7") (pinfunction "BSDA_7") (pintype "bidirectional"))
      (node (ref "SJ2") (pin "3") (pinfunction "3_3") (pintype "passive"))
      (node (ref "SJ3") (pin "3") (pinfunction "3_3") (pintype "passive"))
      (node (ref "UM1") (pin "IO20") (pinfunction "IO20_IO20") (pintype "bidirectional"))
    )
    (net (code "43") (name "/SDAA") (class "Default")
      (node (ref "I2C_1") (pin "3") (pinfunction "3_3") (pintype "passive"))
      (node (ref "I2C_2") (pin "3") (pinfunction "3_3") (pintype "passive"))
      (node (ref "I2C_3") (pin "3") (pinfunction "3_3") (pintype "passive"))
      (node (ref "I2C_4") (pin "3") (pinfunction "3_3") (pintype "passive"))
      (node (ref "SJ3") (pin "2") (pinfunction "2_2") (pintype "passive"))
    )
    (net (code "44") (name "/SDAB") (class "Default")
      (node (ref "I2C_5") (pin "3") (pinfunction "3_3") (pintype "passive"))
      (node (ref "I2C_6") (pin "3") (pinfunction "3_3") (pintype "passive"))
      (node (ref "I2C_7") (pin "3") (pinfunction "3_3") (pintype "passive"))
      (node (ref "SJ2") (pin "2") (pinfunction "2_2") (pintype "passive"))
    )
    (net (code "45") (name "/VIN") (class "Default")
      (node (ref "UM1") (pin "VIN") (pinfunction "VIN_VIN") (pintype "bidirectional"))
      (node (ref "UM2") (pin "PWR_VIN") (pinfunction "VIN_PWR_VIN") (pintype "passive"))
    )
    (net (code "46") (name "GND") (class "Default")
      (node (ref "A0") (pin "1") (pinfunction "1_1") (pintype "passive"))
      (node (ref "A1") (pin "1") (pinfunction "1_1") (pintype "passive"))
      (node (ref "A2") (pin "1") (pinfunction "1_1") (pintype "passive"))
      (node (ref "A3") (pin "1") (pinfunction "1_1") (pintype "passive"))
      (node (ref "A4") (pin "1") (pinfunction "1_1") (pintype "passive"))
      (node (ref "A5") (pin "1") (pinfunction "1_1") (pintype "passive"))
      (node (ref "A6") (pin "1") (pinfunction "1_1") (pintype "passive"))
      (node (ref "A7") (pin "1") (pinfunction "1_1") (pintype "passive"))
      (node (ref "C10") (pin "1") (pinfunction "1_1") (pintype "passive"))
      (node (ref "C11") (pin "N") (pinfunction "N_N") (pintype "passive"))
      (node (ref "C12") (pin "1") (pinfunction "1_1") (pintype "passive"))
      (node (ref "C13") (pin "1") (pinfunction "1_1") (pintype "passive"))
      (node (ref "C14") (pin "1") (pinfunction "1_1") (pintype "passive"))
      (node (ref "C15") (pin "1") (pinfunction "1_1") (pintype "passive"))
      (node (ref "C16") (pin "1") (pinfunction "1_1") (pintype "passive"))
      (node (ref "C5") (pin "1") (pinfunction "1_1") (pintype "passive"))
      (node (ref "D10") (pin "1") (pinfunction "1_1") (pintype "passive"))
      (node (ref "D3") (pin "1") (pinfunction "1_1") (pintype "passive"))
      (node (ref "D4") (pin "1") (pinfunction "1_1") (pintype "passive"))
      (node (ref "D5") (pin "1") (pinfunction "1_1") (pintype "passive"))
      (node (ref "D6") (pin "1") (pinfunction "1_1") (pintype "passive"))
      (node (ref "D7") (pin "1") (pinfunction "1_1") (pintype "passive"))
      (node (ref "D8") (pin "1") (pinfunction "1_1") (pintype "passive"))
      (node (ref "D9") (pin "1") (pinfunction "1_1") (pintype "passive"))
      (node (ref "DCDC1") (pin "1") (pinfunction "GND_1") (pintype "bidirectional"))
      (node (ref "DCDC2") (pin "1") (pinfunction "GND_1") (pintype "bidirectional"))
      (node (ref "GNDA") (pin "1") (pinfunction "MP_1") (pintype "passive"))
      (node (ref "GNDB") (pin "1") (pinfunction "MP_1") (pintype "passive"))
      (node (ref "GNDC") (pin "1") (pinfunction "MP_1") (pintype "passive"))
      (node (ref "GNDD") (pin "1") (pinfunction "MP_1") (pintype "passive"))
      (node (ref "I2C_1") (pin "1") (pinfunction "1_1") (pintype "passive"))
      (node (ref "I2C_2") (pin "1") (pinfunction "1_1") (pintype "passive"))
      (node (ref "I2C_3") (pin "1") (pinfunction "1_1") (pintype "passive"))
      (node (ref "I2C_4") (pin "1") (pinfunction "1_1") (pintype "passive"))
      (node (ref "I2C_5") (pin "1") (pinfunction "1_1") (pintype "passive"))
      (node (ref "I2C_6") (pin "1") (pinfunction "1_1") (pintype "passive"))
      (node (ref "I2C_7") (pin "1") (pinfunction "1_1") (pintype "passive"))
      (node (ref "ICSP") (pin "6") (pinfunction "6_6") (pintype "passive"))
      (node (ref "PWR") (pin "C") (pinfunction "C_C") (pintype "passive"))
      (node (ref "R12") (pin "1") (pinfunction "1_1") (pintype "passive"))
      (node (ref "R13") (pin "1") (pinfunction "1_1") (pintype "passive"))
      (node (ref "SERIAL_1") (pin "1") (pinfunction "1_1") (pintype "passive"))
      (node (ref "SERIAL_2") (pin "1") (pinfunction "1_1") (pintype "passive"))
      (node (ref "SERIAL_3") (pin "1") (pinfunction "1_1") (pintype "passive"))
      (node (ref "SIG_ISO1") (pin "5") (pinfunction "BGND_5") (pintype "bidirectional"))
      (node (ref "SIG_ISO2") (pin "5") (pinfunction "BGND_5") (pintype "bidirectional"))
      (node (ref "SW1") (pin "1A") (pinfunction "PA1_1A") (pintype "passive"))
      (node (ref "SW1") (pin "1B") (pinfunction "PA2_1B") (pintype "passive"))
      (node (ref "UM1") (pin "GND1") (pinfunction "GND1_GND1") (pintype "bidirectional"))
      (node (ref "UM1") (pin "GND2") (pinfunction "GND2_GND2") (pintype "bidirectional"))
      (node (ref "UM1") (pin "GND3") (pinfunction "GND3_GND3") (pintype "bidirectional"))
      (node (ref "UM2") (pin "IOH14") (pinfunction "GND1_IOH14") (pintype "passive"))
      (node (ref "UM2") (pin "PWR_GND2") (pinfunction "GND2_PWR_GND2") (pintype "passive"))
      (node (ref "UM2") (pin "PWR_GND3") (pinfunction "GND3_PWR_GND3") (pintype "passive"))
    )
    (net (code "47") (name "GND_ISO1") (class "Default")
      (node (ref "C1") (pin "2") (pinfunction "2_2") (pintype "passive"))
      (node (ref "C2") (pin "2") (pinfunction "2_2") (pintype "passive"))
      (node (ref "C3") (pin "1") (pinfunction "1_1") (pintype "passive"))
      (node (ref "C4") (pin "1") (pinfunction "1_1") (pintype "passive"))
      (node (ref "DCDC1") (pin "4") (pinfunction "GND_ISO_4") (pintype "bidirectional"))
      (node (ref "REG1") (pin "2") (pinfunction "GND_2") (pintype "bidirectional"))
      (node (ref "REG1") (pin "TAB") (pinfunction "TAB_TAB") (pintype "bidirectional"))
      (node (ref "SIG_ISO1") (pin "4") (pinfunction "AGND_4") (pintype "bidirectional"))
      (node (ref "STP1") (pin "1") (pinfunction "GND_1") (pintype "bidirectional"))
    )
    (net (code "48") (name "GND_ISO2") (class "Default")
      (node (ref "C6") (pin "2") (pinfunction "2_2") (pintype "passive"))
      (node (ref "C7") (pin "2") (pinfunction "2_2") (pintype "passive"))
      (node (ref "C8") (pin "1") (pinfunction "1_1") (pintype "passive"))
      (node (ref "C9") (pin "1") (pinfunction "1_1") (pintype "passive"))
      (node (ref "DCDC2") (pin "4") (pinfunction "GND_ISO_4") (pintype "bidirectional"))
      (node (ref "REG2") (pin "2") (pinfunction "GND_2") (pintype "bidirectional"))
      (node (ref "REG2") (pin "TAB") (pinfunction "TAB_TAB") (pintype "bidirectional"))
      (node (ref "SIG_ISO2") (pin "4") (pinfunction "AGND_4") (pintype "bidirectional"))
      (node (ref "STP2") (pin "1") (pinfunction "GND_1") (pintype "bidirectional"))
    )
    (net (code "49") (name "Net-(DCDC1-V_ISO)") (class "Default")
      (node (ref "C2") (pin "1") (pinfunction "1_1") (pintype "passive"))
      (node (ref "DCDC1") (pin "5") (pinfunction "V_ISO_5") (pintype "bidirectional"))
      (node (ref "REG1") (pin "3") (pinfunction "VIN_3") (pintype "bidirectional"))
    )
    (net (code "50") (name "Net-(DCDC2-V_ISO)") (class "Default")
      (node (ref "C7") (pin "1") (pinfunction "1_1") (pintype "passive"))
      (node (ref "DCDC2") (pin "5") (pinfunction "V_ISO_5") (pintype "bidirectional"))
      (node (ref "REG2") (pin "3") (pinfunction "VIN_3") (pintype "bidirectional"))
    )
    (net (code "51") (name "Net-(P1-G1)") (class "Default")
      (node (ref "P1") (pin "2") (pinfunction "G1_2") (pintype "passive"))
      (node (ref "STP1") (pin "6") (pinfunction "PRB_GND_6") (pintype "bidirectional"))
      (node (ref "SW2") (pin "2") (pinfunction "2_2") (pintype "passive"))
      (node (ref "SW2") (pin "4") (pinfunction "4_4") (pintype "passive"))
    )
    (net (code "52") (name "Net-(P1-P)") (class "Default")
      (node (ref "P1") (pin "1") (pinfunction "P_1") (pintype "passive"))
      (node (ref "STP1") (pin "5") (pinfunction "PRB_5") (pintype "bidirectional"))
    )
    (net (code "53") (name "Net-(P2-G1)") (class "Default")
      (node (ref "P2") (pin "2") (pinfunction "G1_2") (pintype "passive"))
      (node (ref "STP2") (pin "6") (pinfunction "PRB_GND_6") (pintype "bidirectional"))
      (node (ref "SW3") (pin "2") (pinfunction "2_2") (pintype "passive"))
      (node (ref "SW3") (pin "4") (pinfunction "4_4") (pintype "passive"))
    )
    (net (code "54") (name "Net-(P2-P)") (class "Default")
      (node (ref "P2") (pin "1") (pinfunction "P_1") (pintype "passive"))
      (node (ref "STP2") (pin "5") (pinfunction "PRB_5") (pintype "bidirectional"))
    )
    (net (code "55") (name "Net-(PWR-PadA)") (class "Default")
      (node (ref "PWR") (pin "A") (pinfunction "A_A") (pintype "passive"))
      (node (ref "R11") (pin "2") (pinfunction "2_2") (pintype "passive"))
    )
    (net (code "56") (name "Net-(SIG_ISO1-ASCL)") (class "Default")
      (node (ref "R1") (pin "1") (pinfunction "1_1") (pintype "passive"))
      (node (ref "SIG_ISO1") (pin "3") (pinfunction "ASCL_3") (pintype "bidirectional"))
      (node (ref "STP1") (pin "3") (pinfunction "RX_3") (pintype "bidirectional"))
    )
    (net (code "57") (name "Net-(SIG_ISO1-ASDA)") (class "Default")
      (node (ref "R2") (pin "1") (pinfunction "1_1") (pintype "passive"))
      (node (ref "SIG_ISO1") (pin "2") (pinfunction "ASDA_2") (pintype "bidirectional"))
      (node (ref "STP1") (pin "2") (pinfunction "TX_2") (pintype "bidirectional"))
      (node (ref "SW2") (pin "1") (pinfunction "1_1") (pintype "passive"))
      (node (ref "SW2") (pin "3") (pinfunction "3_3") (pintype "passive"))
    )
    (net (code "58") (name "Net-(SIG_ISO2-ASCL)") (class "Default")
      (node (ref "R3") (pin "1") (pinfunction "1_1") (pintype "passive"))
      (node (ref "SIG_ISO2") (pin "3") (pinfunction "ASCL_3") (pintype "bidirectional"))
      (node (ref "STP2") (pin "3") (pinfunction "RX_3") (pintype "bidirectional"))
    )
    (net (code "59") (name "Net-(SIG_ISO2-ASDA)") (class "Default")
      (node (ref "R4") (pin "1") (pinfunction "1_1") (pintype "passive"))
      (node (ref "SIG_ISO2") (pin "2") (pinfunction "ASDA_2") (pintype "bidirectional"))
      (node (ref "STP2") (pin "2") (pinfunction "TX_2") (pintype "bidirectional"))
      (node (ref "SW3") (pin "1") (pinfunction "1_1") (pintype "passive"))
      (node (ref "SW3") (pin "3") (pinfunction "3_3") (pintype "passive"))
    )
    (net (code "60") (name "Net-(STATUS-GC)") (class "Default")
      (node (ref "R13") (pin "2") (pinfunction "2_2") (pintype "passive"))
      (node (ref "STATUS") (pin "4") (pinfunction "GC_4") (pintype "passive"))
    )
    (net (code "61") (name "Net-(STATUS-RC)") (class "Default")
      (node (ref "R12") (pin "2") (pinfunction "2_2") (pintype "passive"))
      (node (ref "STATUS") (pin "2") (pinfunction "RC_2") (pintype "passive"))
    )
    (net (code "62") (name "Net-(UM1-AIN8)") (class "Default")
      (node (ref "JP2") (pin "1") (pinfunction "1_1") (pintype "passive"))
      (node (ref "UM1") (pin "ADH0") (pinfunction "AIN8_ADH0") (pintype "bidirectional"))
    )
    (net (code "63") (name "Net-(UM1-AIN9)") (class "Default")
      (node (ref "JP2") (pin "2") (pinfunction "2_2") (pintype "passive"))
      (node (ref "UM1") (pin "ADH1") (pinfunction "AIN9_ADH1") (pintype "bidirectional"))
    )
    (net (code "64") (name "Net-(UM1-AIN10)") (class "Default")
      (node (ref "JP2") (pin "3") (pinfunction "3_3") (pintype "passive"))
      (node (ref "UM1") (pin "ADH2") (pinfunction "AIN10_ADH2") (pintype "bidirectional"))
    )
    (net (code "65") (name "Net-(UM1-AIN11)") (class "Default")
      (node (ref "JP2") (pin "4") (pinfunction "4_4") (pintype "passive"))
      (node (ref "UM1") (pin "ADH3") (pinfunction "AIN11_ADH3") (pintype "bidirectional"))
    )
    (net (code "66") (name "Net-(UM1-AIN12)") (class "Default")
      (node (ref "JP2") (pin "5") (pinfunction "5_5") (pintype "passive"))
      (node (ref "UM1") (pin "ADH4") (pinfunction "AIN12_ADH4") (pintype "bidirectional"))
    )
    (net (code "67") (name "Net-(UM1-AIN13)") (class "Default")
      (node (ref "JP2") (pin "6") (pinfunction "6_6") (pintype "passive"))
      (node (ref "UM1") (pin "ADH5") (pinfunction "AIN13_ADH5") (pintype "bidirectional"))
    )
    (net (code "68") (name "Net-(UM1-AIN14)") (class "Default")
      (node (ref "JP2") (pin "7") (pinfunction "7_7") (pintype "passive"))
      (node (ref "UM1") (pin "ADH6") (pinfunction "AIN14_ADH6") (pintype "bidirectional"))
    )
    (net (code "69") (name "Net-(UM1-AIN15)") (class "Default")
      (node (ref "JP2") (pin "8") (pinfunction "8_8") (pintype "passive"))
      (node (ref "UM1") (pin "ADH7") (pinfunction "AIN15_ADH7") (pintype "bidirectional"))
    )
    (net (code "70") (name "VCOM") (class "Default")
      (node (ref "C10") (pin "2") (pinfunction "2_2") (pintype "passive"))
      (node (ref "C5") (pin "2") (pinfunction "2_2") (pintype "passive"))
      (node (ref "R5") (pin "2") (pinfunction "2_2") (pintype "passive"))
      (node (ref "R6") (pin "2") (pinfunction "2_2") (pintype "passive"))
      (node (ref "SIG_ISO1") (pin "8") (pinfunction "BVDD_8") (pintype "bidirectional"))
      (node (ref "SIG_ISO2") (pin "8") (pinfunction "BVDD_8") (pintype "bidirectional"))
      (node (ref "UM1") (pin "IRF") (pinfunction "IOREF_IRF") (pintype "bidirectional"))
      (node (ref "UM2") (pin "PWR_IOREF") (pinfunction "IOREF_PWR_IOREF") (pintype "passive"))
    )
    (net (code "71") (name "V_ISO1") (class "Default")
      (node (ref "C1") (pin "1") (pinfunction "1_1") (pintype "passive"))
      (node (ref "C3") (pin "2") (pinfunction "2_2") (pintype "passive"))
      (node (ref "C4") (pin "2") (pinfunction "2_2") (pintype "passive"))
      (node (ref "R1") (pin "2") (pinfunction "2_2") (pintype "passive"))
      (node (ref "R2") (pin "2") (pinfunction "2_2") (pintype "passive"))
      (node (ref "REG1") (pin "1") (pinfunction "VOUT_1") (pintype "bidirectional"))
      (node (ref "SIG_ISO1") (pin "1") (pinfunction "AVDD_1") (pintype "bidirectional"))
      (node (ref "STP1") (pin "4") (pinfunction "VCC_4") (pintype "bidirectional"))
    )
    (net (code "72") (name "V_ISO2") (class "Default")
      (node (ref "C6") (pin "1") (pinfunction "1_1") (pintype "passive"))
      (node (ref "C8") (pin "2") (pinfunction "2_2") (pintype "passive"))
      (node (ref "C9") (pin "2") (pinfunction "2_2") (pintype "passive"))
      (node (ref "R3") (pin "2") (pinfunction "2_2") (pintype "passive"))
      (node (ref "R4") (pin "2") (pinfunction "2_2") (pintype "passive"))
      (node (ref "REG2") (pin "1") (pinfunction "VOUT_1") (pintype "bidirectional"))
      (node (ref "SIG_ISO2") (pin "1") (pinfunction "AVDD_1") (pintype "bidirectional"))
      (node (ref "STP2") (pin "4") (pinfunction "VCC_4") (pintype "bidirectional"))
    )
    (net (code "73") (name "unconnected-(A0-Pad4)") (class "Default")
      (node (ref "A0") (pin "4") (pinfunction "4_4") (pintype "passive"))
    )
    (net (code "74") (name "unconnected-(A1-Pad4)") (class "Default")
      (node (ref "A1") (pin "4") (pinfunction "4_4") (pintype "passive"))
    )
    (net (code "75") (name "unconnected-(A2-Pad4)") (class "Default")
      (node (ref "A2") (pin "4") (pinfunction "4_4") (pintype "passive"))
    )
    (net (code "76") (name "unconnected-(A3-Pad4)") (class "Default")
      (node (ref "A3") (pin "4") (pinfunction "4_4") (pintype "passive"))
    )
    (net (code "77") (name "unconnected-(A4-Pad4)") (class "Default")
      (node (ref "A4") (pin "4") (pinfunction "4_4") (pintype "passive"))
    )
    (net (code "78") (name "unconnected-(A5-Pad4)") (class "Default")
      (node (ref "A5") (pin "4") (pinfunction "4_4") (pintype "passive"))
    )
    (net (code "79") (name "unconnected-(A6-Pad4)") (class "Default")
      (node (ref "A6") (pin "4") (pinfunction "4_4") (pintype "passive"))
    )
    (net (code "80") (name "unconnected-(A7-Pad4)") (class "Default")
      (node (ref "A7") (pin "4") (pinfunction "4_4") (pintype "passive"))
    )
    (net (code "81") (name "unconnected-(D3-Pad4)") (class "Default")
      (node (ref "D3") (pin "4") (pinfunction "4_4") (pintype "passive"))
    )
    (net (code "82") (name "unconnected-(D4-Pad4)") (class "Default")
      (node (ref "D4") (pin "4") (pinfunction "4_4") (pintype "passive"))
    )
    (net (code "83") (name "unconnected-(D5-Pad4)") (class "Default")
      (node (ref "D5") (pin "4") (pinfunction "4_4") (pintype "passive"))
    )
    (net (code "84") (name "unconnected-(D6-Pad4)") (class "Default")
      (node (ref "D6") (pin "4") (pinfunction "4_4") (pintype "passive"))
    )
    (net (code "85") (name "unconnected-(D7-Pad4)") (class "Default")
      (node (ref "D7") (pin "4") (pinfunction "4_4") (pintype "passive"))
    )
    (net (code "86") (name "unconnected-(D8-Pad4)") (class "Default")
      (node (ref "D8") (pin "4") (pinfunction "4_4") (pintype "passive"))
    )
    (net (code "87") (name "unconnected-(D9-Pad4)") (class "Default")
      (node (ref "D9") (pin "4") (pinfunction "4_4") (pintype "passive"))
    )
    (net (code "88") (name "unconnected-(D10-Pad4)") (class "Default")
      (node (ref "D10") (pin "4") (pinfunction "4_4") (pintype "passive"))
    )
    (net (code "89") (name "unconnected-(DCDC1-NC1-Pad3)") (class "Default")
      (node (ref "DCDC1") (pin "3") (pinfunction "NC1_3") (pintype "bidirectional"))
    )
    (net (code "90") (name "unconnected-(DCDC1-NC2-Pad6)") (class "Default")
      (node (ref "DCDC1") (pin "6") (pinfunction "NC2_6") (pintype "bidirectional"))
    )
    (net (code "91") (name "unconnected-(DCDC1-NC3-Pad7)") (class "Default")
      (node (ref "DCDC1") (pin "7") (pinfunction "NC3_7") (pintype "bidirectional"))
    )
    (net (code "92") (name "unconnected-(DCDC1-NC4-Pad8)") (class "Default")
      (node (ref "DCDC1") (pin "8") (pinfunction "NC4_8") (pintype "bidirectional"))
    )
    (net (code "93") (name "unconnected-(DCDC2-NC1-Pad3)") (class "Default")
      (node (ref "DCDC2") (pin "3") (pinfunction "NC1_3") (pintype "bidirectional"))
    )
    (net (code "94") (name "unconnected-(DCDC2-NC2-Pad6)") (class "Default")
      (node (ref "DCDC2") (pin "6") (pinfunction "NC2_6") (pintype "bidirectional"))
    )
    (net (code "95") (name "unconnected-(DCDC2-NC3-Pad7)") (class "Default")
      (node (ref "DCDC2") (pin "7") (pinfunction "NC3_7") (pintype "bidirectional"))
    )
    (net (code "96") (name "unconnected-(DCDC2-NC4-Pad8)") (class "Default")
      (node (ref "DCDC2") (pin "8") (pinfunction "NC4_8") (pintype "bidirectional"))
    )
    (net (code "97") (name "unconnected-(SW2-GPIN-PadGP)") (class "Default")
      (node (ref "SW2") (pin "GP") (pinfunction "GPIN_GP") (pintype "passive"))
    )
    (net (code "98") (name "unconnected-(SW3-GPIN-PadGP)") (class "Default")
      (node (ref "SW3") (pin "GP") (pinfunction "GPIN_GP") (pintype "passive"))
    )
  )
)
